# 2021-04-14_BOSS-RoboClaw-Breakout.net
KiCad netlist of a schematic drawn in EAGLE
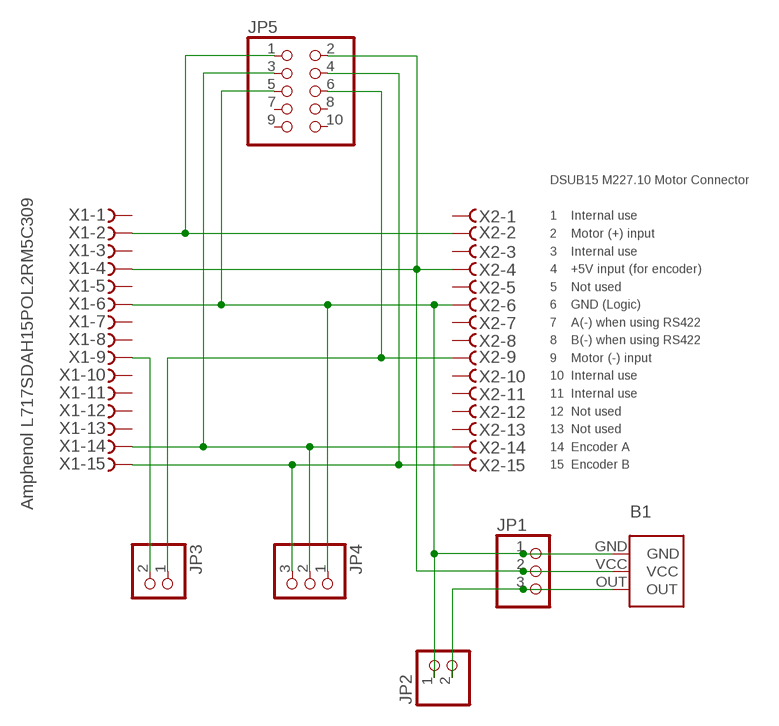
[diagram p0: schematic, sheet 1]

(export (version "E")
  (design (tool "Eeschema 10.0.6"))
  (components
    (comp (ref "B1")
      (value "ACS724CARRIER")
      (footprint "eagle-import:ACS724CARRIER")
      (libsource (lib "eagle-import") (part "ACS724CARRIER"))
    )
    (comp (ref "JP1")
      (value "PINHD-1X3")
      (footprint "eagle-import:1X03")
      (libsource (lib "eagle-import") (part "PINHD-1X3"))
    )
    (comp (ref "JP2")
      (value "PINHD-1X2")
      (footprint "eagle-import:1X02")
      (libsource (lib "eagle-import") (part "PINHD-1X2"))
    )
    (comp (ref "JP3")
      (value "PINHD-1X2")
      (footprint "eagle-import:1X02")
      (libsource (lib "eagle-import") (part "PINHD-1X2"))
    )
    (comp (ref "JP4")
      (value "PINHD-1X3")
      (footprint "eagle-import:1X03")
      (libsource (lib "eagle-import") (part "PINHD-1X3"))
    )
    (comp (ref "JP5")
      (value "PINHD-2X5")
      (footprint "eagle-import:2X05")
      (libsource (lib "eagle-import") (part "PINHD-2X5"))
    )
    (comp (ref "X1")
      (value "Amphenol L717SDAH15POL2RM5C309")
      (footprint "eagle-import:H2M15ST")
      (libsource (lib "eagle-import") (part "D-SUB15-H2M15ST"))
    )
    (comp (ref "X2")
      (value "Amphenol L77SDAH15SOL2RM8C309")
      (footprint "eagle-import:H2R15ST")
      (libsource (lib "eagle-import") (part "D-SUB15-H2R15ST"))
    )
  )
  (nets
    (net (code "1") (name "Net-(B1-PadOUT)") (class "Default")
      (node (ref "B1") (pin "OUT") (pinfunction "OUT_OUT") (pintype "bidirectional"))
      (node (ref "JP1") (pin "3") (pinfunction "3_3") (pintype "passive"))
      (node (ref "JP2") (pin "2") (pinfunction "2_2") (pintype "passive"))
    )
    (net (code "2") (name "Net-(X1F-F)") (class "Default")
      (node (ref "JP4") (pin "2") (pinfunction "2_2") (pintype "passive"))
      (node (ref "JP5") (pin "3") (pinfunction "3_3") (pintype "passive"))
      (node (ref "X1") (pin "14") (pinfunction "F_14") (pintype "passive"))
      (node (ref "X2") (pin "14") (pinfunction "F_14") (pintype "passive"))
    )
    (net (code "3") (name "Net-(X1G-F)") (class "Default")
      (node (ref "JP4") (pin "3") (pinfunction "3_3") (pintype "passive"))
      (node (ref "JP5") (pin "4") (pinfunction "4_4") (pintype "passive"))
      (node (ref "X1") (pin "15") (pinfunction "F_15") (pintype "passive"))
      (node (ref "X2") (pin "15") (pinfunction "F_15") (pintype "passive"))
    )
    (net (code "4") (name "Net-(X1H-F)") (class "Default")
      (node (ref "JP5") (pin "1") (pinfunction "1_1") (pintype "passive"))
      (node (ref "X1") (pin "2") (pinfunction "F_2") (pintype "passive"))
      (node (ref "X2") (pin "2") (pinfunction "F_2") (pintype "passive"))
    )
    (net (code "5") (name "Net-(X1J-F)") (class "Default")
      (node (ref "B1") (pin "VCC") (pinfunction "VCC_VCC") (pintype "bidirectional"))
      (node (ref "JP1") (pin "2") (pinfunction "2_2") (pintype "passive"))
      (node (ref "JP5") (pin "2") (pinfunction "2_2") (pintype "passive"))
      (node (ref "X1") (pin "4") (pinfunction "F_4") (pintype "passive"))
      (node (ref "X2") (pin "4") (pinfunction "F_4") (pintype "passive"))
    )
    (net (code "6") (name "Net-(X1L-F)") (class "Default")
      (node (ref "B1") (pin "GND") (pinfunction "GND_GND") (pintype "bidirectional"))
      (node (ref "JP1") (pin "1") (pinfunction "1_1") (pintype "passive"))
      (node (ref "JP2") (pin "1") (pinfunction "1_1") (pintype "passive"))
      (node (ref "JP4") (pin "1") (pinfunction "1_1") (pintype "passive"))
      (node (ref "JP5") (pin "5") (pinfunction "5_5") (pintype "passive"))
      (node (ref "X1") (pin "6") (pinfunction "F_6") (pintype "passive"))
      (node (ref "X2") (pin "6") (pinfunction "F_6") (pintype "passive"))
    )
    (net (code "7") (name "Net-(X1O-F)") (class "Default")
      (node (ref "JP3") (pin "2") (pinfunction "2_2") (pintype "passive"))
      (node (ref "X1") (pin "9") (pinfunction "F_9") (pintype "passive"))
    )
    (net (code "8") (name "Net-(X2O-F)") (class "Default")
      (node (ref "JP3") (pin "1") (pinfunction "1_1") (pintype "passive"))
      (node (ref "JP5") (pin "6") (pinfunction "6_6") (pintype "passive"))
      (node (ref "X2") (pin "9") (pinfunction "F_9") (pintype "passive"))
    )
    (net (code "9") (name "unconnected-(JP5-Pad7)") (class "Default")
      (node (ref "JP5") (pin "7") (pinfunction "7_7") (pintype "passive"))
    )
    (net (code "10") (name "unconnected-(JP5-Pad8)") (class "Default")
      (node (ref "JP5") (pin "8") (pinfunction "8_8") (pintype "passive"))
    )
    (net (code "11") (name "unconnected-(JP5-Pad9)") (class "Default")
      (node (ref "JP5") (pin "9") (pinfunction "9_9") (pintype "passive"))
    )
    (net (code "12") (name "unconnected-(JP5-Pad10)") (class "Default")
      (node (ref "JP5") (pin "10") (pinfunction "10_10") (pintype "passive"))
    )
    (net (code "13") (name "unconnected-(X1A-F-Pad1)") (class "Default")
      (node (ref "X1") (pin "1") (pinfunction "F_1") (pintype "passive"))
    )
    (net (code "14") (name "unconnected-(X1B-F-Pad10)") (class "Default")
      (node (ref "X1") (pin "10") (pinfunction "F_10") (pintype "passive"))
    )
    (net (code "15") (name "unconnected-(X1C-F-Pad11)") (class "Default")
      (node (ref "X1") (pin "11") (pinfunction "F_11") (pintype "passive"))
    )
    (net (code "16") (name "unconnected-(X1D-F-Pad12)") (class "Default")
      (node (ref "X1") (pin "12") (pinfunction "F_12") (pintype "passive"))
    )
    (net (code "17") (name "unconnected-(X1E-F-Pad13)") (class "Default")
      (node (ref "X1") (pin "13") (pinfunction "F_13") (pintype "passive"))
    )
    (net (code "18") (name "unconnected-(X1I-F-Pad3)") (class "Default")
      (node (ref "X1") (pin "3") (pinfunction "F_3") (pintype "passive"))
    )
    (net (code "19") (name "unconnected-(X1K-F-Pad5)") (class "Default")
      (node (ref "X1") (pin "5") (pinfunction "F_5") (pintype "passive"))
    )
    (net (code "20") (name "unconnected-(X1M-F-Pad7)") (class "Default")
      (node (ref "X1") (pin "7") (pinfunction "F_7") (pintype "passive"))
    )
    (net (code "21") (name "unconnected-(X1N-F-Pad8)") (class "Default")
      (node (ref "X1") (pin "8") (pinfunction "F_8") (pintype "passive"))
    )
    (net (code "22") (name "unconnected-(X2A-F-Pad1)") (class "Default")
      (node (ref "X2") (pin "1") (pinfunction "F_1") (pintype "passive"))
    )
    (net (code "23") (name "unconnected-(X2B-F-Pad10)") (class "Default")
      (node (ref "X2") (pin "10") (pinfunction "F_10") (pintype "passive"))
    )
    (net (code "24") (name "unconnected-(X2C-F-Pad11)") (class "Default")
      (node (ref "X2") (pin "11") (pinfunction "F_11") (pintype "passive"))
    )
    (net (code "25") (name "unconnected-(X2D-F-Pad12)") (class "Default")
      (node (ref "X2") (pin "12") (pinfunction "F_12") (pintype "passive"))
    )
    (net (code "26") (name "unconnected-(X2E-F-Pad13)") (class "Default")
      (node (ref "X2") (pin "13") (pinfunction "F_13") (pintype "passive"))
    )
    (net (code "27") (name "unconnected-(X2I-F-Pad3)") (class "Default")
      (node (ref "X2") (pin "3") (pinfunction "F_3") (pintype "passive"))
    )
    (net (code "28") (name "unconnected-(X2K-F-Pad5)") (class "Default")
      (node (ref "X2") (pin "5") (pinfunction "F_5") (pintype "passive"))
    )
    (net (code "29") (name "unconnected-(X2M-F-Pad7)") (class "Default")
      (node (ref "X2") (pin "7") (pinfunction "F_7") (pintype "passive"))
    )
    (net (code "30") (name "unconnected-(X2N-F-Pad8)") (class "Default")
      (node (ref "X2") (pin "8") (pinfunction "F_8") (pintype "passive"))
    )
  )
)
